# picotouch_synth.net
KiCad netlist of a schematic drawn in EAGLE
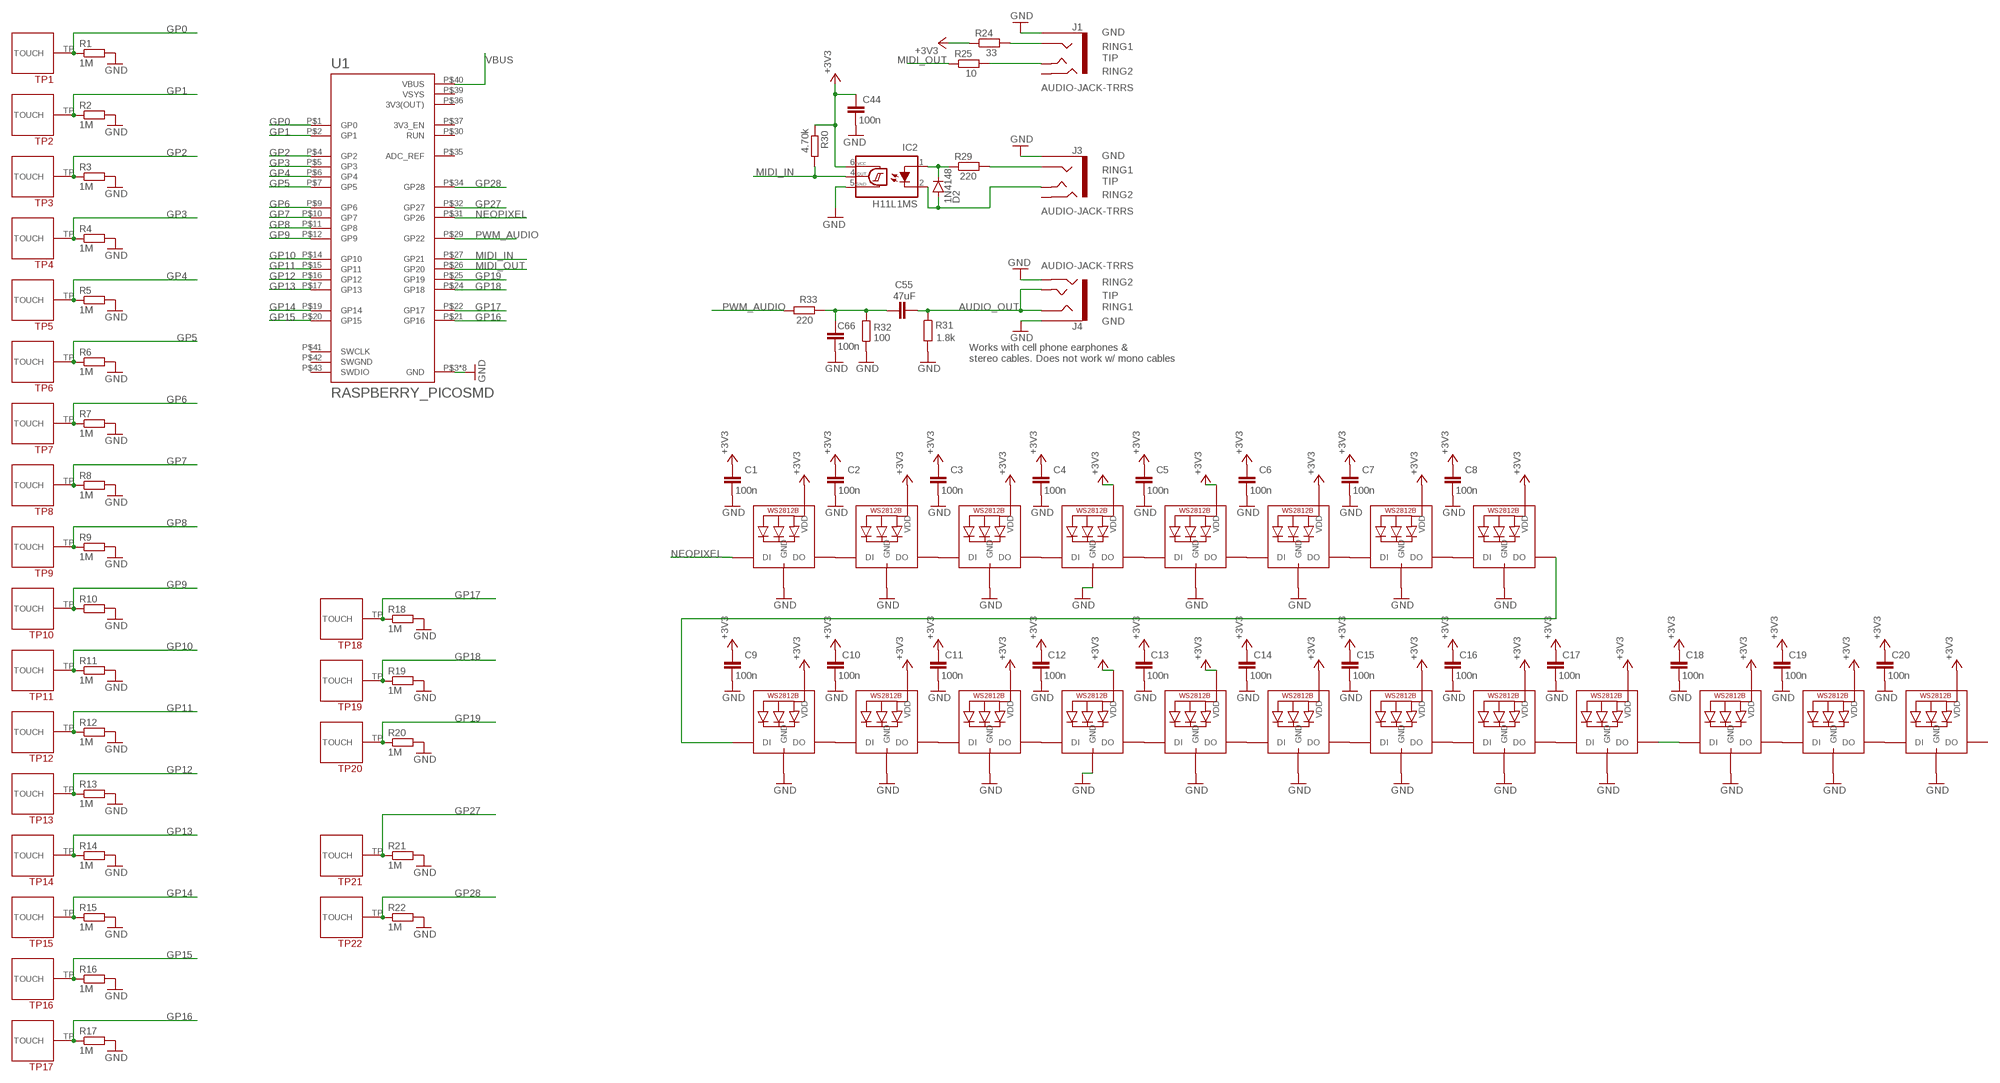
[diagram p0: schematic, sheet 1]

(export (version "E")
  (design (tool "Eeschema 10.0.6"))
  (components
    (comp (ref "C1")
      (value "100n")
      (footprint "eagle-import:C0603")
      (libsource (lib "eagle-import") (part "C-EUC0603"))
    )
    (comp (ref "C2")
      (value "100n")
      (footprint "eagle-import:C0603")
      (libsource (lib "eagle-import") (part "C-EUC0603"))
    )
    (comp (ref "C3")
      (value "100n")
      (footprint "eagle-import:C0603")
      (libsource (lib "eagle-import") (part "C-EUC0603"))
    )
    (comp (ref "C4")
      (value "100n")
      (footprint "eagle-import:C0603")
      (libsource (lib "eagle-import") (part "C-EUC0603"))
    )
    (comp (ref "C5")
      (value "100n")
      (footprint "eagle-import:C0603")
      (libsource (lib "eagle-import") (part "C-EUC0603"))
    )
    (comp (ref "C6")
      (value "100n")
      (footprint "eagle-import:C0603")
      (libsource (lib "eagle-import") (part "C-EUC0603"))
    )
    (comp (ref "C7")
      (value "100n")
      (footprint "eagle-import:C0603")
      (libsource (lib "eagle-import") (part "C-EUC0603"))
    )
    (comp (ref "C8")
      (value "100n")
      (footprint "eagle-import:C0603")
      (libsource (lib "eagle-import") (part "C-EUC0603"))
    )
    (comp (ref "C9")
      (value "100n")
      (footprint "eagle-import:C0603")
      (libsource (lib "eagle-import") (part "C-EUC0603"))
    )
    (comp (ref "C10")
      (value "100n")
      (footprint "eagle-import:C0603")
      (libsource (lib "eagle-import") (part "C-EUC0603"))
    )
    (comp (ref "C11")
      (value "100n")
      (footprint "eagle-import:C0603")
      (libsource (lib "eagle-import") (part "C-EUC0603"))
    )
    (comp (ref "C12")
      (value "100n")
      (footprint "eagle-import:C0603")
      (libsource (lib "eagle-import") (part "C-EUC0603"))
    )
    (comp (ref "C13")
      (value "100n")
      (footprint "eagle-import:C0603")
      (libsource (lib "eagle-import") (part "C-EUC0603"))
    )
    (comp (ref "C14")
      (value "100n")
      (footprint "eagle-import:C0603")
      (libsource (lib "eagle-import") (part "C-EUC0603"))
    )
    (comp (ref "C15")
      (value "100n")
      (footprint "eagle-import:C0603")
      (libsource (lib "eagle-import") (part "C-EUC0603"))
    )
    (comp (ref "C16")
      (value "100n")
      (footprint "eagle-import:C0603")
      (libsource (lib "eagle-import") (part "C-EUC0603"))
    )
    (comp (ref "C17")
      (value "100n")
      (footprint "eagle-import:C0603")
      (libsource (lib "eagle-import") (part "C-EUC0603"))
    )
    (comp (ref "C18")
      (value "100n")
      (footprint "eagle-import:C0603")
      (libsource (lib "eagle-import") (part "C-EUC0603"))
    )
    (comp (ref "C19")
      (value "100n")
      (footprint "eagle-import:C0603")
      (libsource (lib "eagle-import") (part "C-EUC0603"))
    )
    (comp (ref "C20")
      (value "100n")
      (footprint "eagle-import:C0603")
      (libsource (lib "eagle-import") (part "C-EUC0603"))
    )
    (comp (ref "C44")
      (value "100n")
      (footprint "eagle-import:C0603")
      (libsource (lib "eagle-import") (part "C-EUC0603"))
    )
    (comp (ref "C55")
      (value "47uF")
      (footprint "eagle-import:C0603")
      (libsource (lib "eagle-import") (part "C-EUC0603"))
    )
    (comp (ref "C66")
      (value "100n")
      (footprint "eagle-import:C0603")
      (libsource (lib "eagle-import") (part "C-EUC0603"))
    )
    (comp (ref "D2")
      (value "1N4148")
      (footprint "eagle-import:SOD123")
      (libsource (lib "eagle-import") (part "DIODE-SOD123"))
    )
    (comp (ref "IC2")
      (value "H11L1MS")
      (footprint "eagle-import:DIL6-SMD")
      (libsource (lib "eagle-import") (part "H11LMS1"))
    )
    (comp (ref "J1")
      (value "AUDIO-JACK-TRRS")
      (footprint "eagle-import:PJ-320D_SPARKFUN")
      (fields (field (name "MPN") "PJ-320D"))
      (libsource (lib "eagle-import") (part "AUDIO-JACK-TRRS"))
    )
    (comp (ref "J3")
      (value "AUDIO-JACK-TRRS")
      (footprint "eagle-import:PJ-320D_SPARKFUN")
      (fields (field (name "MPN") "PJ-320D"))
      (libsource (lib "eagle-import") (part "AUDIO-JACK-TRRS"))
    )
    (comp (ref "J4")
      (value "AUDIO-JACK-TRRS")
      (footprint "eagle-import:PJ-320D_SPARKFUN")
      (fields (field (name "MPN") "PJ-320D") (field (name "LCSC") "C431535"))
      (libsource (lib "eagle-import") (part "AUDIO-JACK-TRRS"))
    )
    (comp (ref "LED1")
      (value "WS2812B3535")
      (footprint "eagle-import:LED3535")
      (libsource (lib "eagle-import") (part "WS2812B3535"))
    )
    (comp (ref "LED2")
      (value "WS2812B3535")
      (footprint "eagle-import:LED3535")
      (libsource (lib "eagle-import") (part "WS2812B3535"))
    )
    (comp (ref "LED3")
      (value "WS2812B3535")
      (footprint "eagle-import:LED3535")
      (libsource (lib "eagle-import") (part "WS2812B3535"))
    )
    (comp (ref "LED4")
      (value "WS2812B3535")
      (footprint "eagle-import:LED3535")
      (libsource (lib "eagle-import") (part "WS2812B3535"))
    )
    (comp (ref "LED5")
      (value "WS2812B3535")
      (footprint "eagle-import:LED3535")
      (libsource (lib "eagle-import") (part "WS2812B3535"))
    )
    (comp (ref "LED6")
      (value "WS2812B3535")
      (footprint "eagle-import:LED3535")
      (libsource (lib "eagle-import") (part "WS2812B3535"))
    )
    (comp (ref "LED7")
      (value "WS2812B3535")
      (footprint "eagle-import:LED3535")
      (libsource (lib "eagle-import") (part "WS2812B3535"))
    )
    (comp (ref "LED8")
      (value "WS2812B3535")
      (footprint "eagle-import:LED3535")
      (libsource (lib "eagle-import") (part "WS2812B3535"))
    )
    (comp (ref "LED9")
      (value "WS2812B3535")
      (footprint "eagle-import:LED3535")
      (libsource (lib "eagle-import") (part "WS2812B3535"))
    )
    (comp (ref "LED10")
      (value "WS2812B3535")
      (footprint "eagle-import:LED3535")
      (libsource (lib "eagle-import") (part "WS2812B3535"))
    )
    (comp (ref "LED11")
      (value "WS2812B3535")
      (footprint "eagle-import:LED3535")
      (libsource (lib "eagle-import") (part "WS2812B3535"))
    )
    (comp (ref "LED12")
      (value "WS2812B3535")
      (footprint "eagle-import:LED3535")
      (libsource (lib "eagle-import") (part "WS2812B3535"))
    )
    (comp (ref "LED13")
      (value "WS2812B3535")
      (footprint "eagle-import:LED3535")
      (libsource (lib "eagle-import") (part "WS2812B3535"))
    )
    (comp (ref "LED14")
      (value "WS2812B3535")
      (footprint "eagle-import:LED3535")
      (libsource (lib "eagle-import") (part "WS2812B3535"))
    )
    (comp (ref "LED15")
      (value "WS2812B3535")
      (footprint "eagle-import:LED3535")
      (libsource (lib "eagle-import") (part "WS2812B3535"))
    )
    (comp (ref "LED16")
      (value "WS2812B3535")
      (footprint "eagle-import:LED3535")
      (libsource (lib "eagle-import") (part "WS2812B3535"))
    )
    (comp (ref "LED17")
      (value "WS2812B3535")
      (footprint "eagle-import:LED3535")
      (libsource (lib "eagle-import") (part "WS2812B3535"))
    )
    (comp (ref "LED18")
      (value "WS2812B3535")
      (footprint "eagle-import:LED3535")
      (libsource (lib "eagle-import") (part "WS2812B3535"))
    )
    (comp (ref "LED19")
      (value "WS2812B3535")
      (footprint "eagle-import:LED3535")
      (libsource (lib "eagle-import") (part "WS2812B3535"))
    )
    (comp (ref "LED20")
      (value "WS2812B3535")
      (footprint "eagle-import:LED3535")
      (libsource (lib "eagle-import") (part "WS2812B3535"))
    )
    (comp (ref "R1")
      (value "1M")
      (footprint "eagle-import:R0805")
      (libsource (lib "eagle-import") (part "R-EU_R0805"))
    )
    (comp (ref "R2")
      (value "1M")
      (footprint "eagle-import:R0805")
      (libsource (lib "eagle-import") (part "R-EU_R0805"))
    )
    (comp (ref "R3")
      (value "1M")
      (footprint "eagle-import:R0805")
      (libsource (lib "eagle-import") (part "R-EU_R0805"))
    )
    (comp (ref "R4")
      (value "1M")
      (footprint "eagle-import:R0805")
      (libsource (lib "eagle-import") (part "R-EU_R0805"))
    )
    (comp (ref "R5")
      (value "1M")
      (footprint "eagle-import:R0805")
      (libsource (lib "eagle-import") (part "R-EU_R0805"))
    )
    (comp (ref "R6")
      (value "1M")
      (footprint "eagle-import:R0805")
      (libsource (lib "eagle-import") (part "R-EU_R0805"))
    )
    (comp (ref "R7")
      (value "1M")
      (footprint "eagle-import:R0805")
      (libsource (lib "eagle-import") (part "R-EU_R0805"))
    )
    (comp (ref "R8")
      (value "1M")
      (footprint "eagle-import:R0805")
      (libsource (lib "eagle-import") (part "R-EU_R0805"))
    )
    (comp (ref "R9")
      (value "1M")
      (footprint "eagle-import:R0805")
      (libsource (lib "eagle-import") (part "R-EU_R0805"))
    )
    (comp (ref "R10")
      (value "R-EU_R0805")
      (footprint "eagle-import:R0805")
      (libsource (lib "eagle-import") (part "R-EU_R0805"))
    )
    (comp (ref "R11")
      (value "1M")
      (footprint "eagle-import:R0805")
      (libsource (lib "eagle-import") (part "R-EU_R0805"))
    )
    (comp (ref "R12")
      (value "1M")
      (footprint "eagle-import:R0805")
      (libsource (lib "eagle-import") (part "R-EU_R0805"))
    )
    (comp (ref "R13")
      (value "1M")
      (footprint "eagle-import:R0805")
      (libsource (lib "eagle-import") (part "R-EU_R0805"))
    )
    (comp (ref "R14")
      (value "1M")
      (footprint "eagle-import:R0805")
      (libsource (lib "eagle-import") (part "R-EU_R0805"))
    )
    (comp (ref "R15")
      (value "1M")
      (footprint "eagle-import:R0805")
      (libsource (lib "eagle-import") (part "R-EU_R0805"))
    )
    (comp (ref "R16")
      (value "1M")
      (footprint "eagle-import:R0805")
      (libsource (lib "eagle-import") (part "R-EU_R0805"))
    )
    (comp (ref "R17")
      (value "1M")
      (footprint "eagle-import:R0805")
      (libsource (lib "eagle-import") (part "R-EU_R0805"))
    )
    (comp (ref "R18")
      (value "1M")
      (footprint "eagle-import:R0603")
      (libsource (lib "eagle-import") (part "R-EU_R0603"))
    )
    (comp (ref "R19")
      (value "1M")
      (footprint "eagle-import:R0603")
      (libsource (lib "eagle-import") (part "R-EU_R0603"))
    )
    (comp (ref "R20")
      (value "1M")
      (footprint "eagle-import:R0603")
      (libsource (lib "eagle-import") (part "R-EU_R0603"))
    )
    (comp (ref "R21")
      (value "1M")
      (footprint "eagle-import:R0603")
      (libsource (lib "eagle-import") (part "R-EU_R0603"))
    )
    (comp (ref "R22")
      (value "1M")
      (footprint "eagle-import:R0603")
      (libsource (lib "eagle-import") (part "R-EU_R0603"))
    )
    (comp (ref "R24")
      (value "33")
      (footprint "eagle-import:R0603")
      (libsource (lib "eagle-import") (part "R-EU_R0603"))
    )
    (comp (ref "R25")
      (value "10")
      (footprint "eagle-import:R0603")
      (libsource (lib "eagle-import") (part "R-EU_R0603"))
    )
    (comp (ref "R29")
      (value "220")
      (footprint "eagle-import:R0603")
      (libsource (lib "eagle-import") (part "R-EU_R0603"))
    )
    (comp (ref "R30")
      (value "4.70k")
      (footprint "eagle-import:R0603")
      (libsource (lib "eagle-import") (part "R-EU_R0603"))
    )
    (comp (ref "R31")
      (value "1.8k")
      (footprint "eagle-import:R0603")
      (libsource (lib "eagle-import") (part "R-EU_R0603"))
    )
    (comp (ref "R32")
      (value "100")
      (footprint "eagle-import:R0603")
      (libsource (lib "eagle-import") (part "R-EU_R0603"))
    )
    (comp (ref "R33")
      (value "220")
      (footprint "eagle-import:R0603")
      (libsource (lib "eagle-import") (part "R-EU_R0603"))
    )
    (comp (ref "TP1")
      (value "TOUCHPADA")
      (footprint "eagle-import:TOUCHPADA")
      (libsource (lib "eagle-import") (part "TOUCHPADA"))
    )
    (comp (ref "TP2")
      (value "TOUCHPADA")
      (footprint "eagle-import:TOUCHPADA")
      (libsource (lib "eagle-import") (part "TOUCHPADA"))
    )
    (comp (ref "TP3")
      (value "TOUCHPADA")
      (footprint "eagle-import:TOUCHPADA")
      (libsource (lib "eagle-import") (part "TOUCHPADA"))
    )
    (comp (ref "TP4")
      (value "TOUCHPADA")
      (footprint "eagle-import:TOUCHPADA")
      (libsource (lib "eagle-import") (part "TOUCHPADA"))
    )
    (comp (ref "TP5")
      (value "TOUCHPADA")
      (footprint "eagle-import:TOUCHPADA")
      (libsource (lib "eagle-import") (part "TOUCHPADA"))
    )
    (comp (ref "TP6")
      (value "TOUCHPADA")
      (footprint "eagle-import:TOUCHPADA")
      (libsource (lib "eagle-import") (part "TOUCHPADA"))
    )
    (comp (ref "TP7")
      (value "TOUCHPADA")
      (footprint "eagle-import:TOUCHPADA")
      (libsource (lib "eagle-import") (part "TOUCHPADA"))
    )
    (comp (ref "TP8")
      (value "TOUCHPADA")
      (footprint "eagle-import:TOUCHPADA")
      (libsource (lib "eagle-import") (part "TOUCHPADA"))
    )
    (comp (ref "TP9")
      (value "TOUCHPADA")
      (footprint "eagle-import:TOUCHPADA")
      (libsource (lib "eagle-import") (part "TOUCHPADA"))
    )
    (comp (ref "TP10")
      (value "TOUCHPADA")
      (footprint "eagle-import:TOUCHPADA")
      (libsource (lib "eagle-import") (part "TOUCHPADA"))
    )
    (comp (ref "TP11")
      (value "TOUCHPADA")
      (footprint "eagle-import:TOUCHPADA")
      (libsource (lib "eagle-import") (part "TOUCHPADA"))
    )
    (comp (ref "TP12")
      (value "TOUCHPADA")
      (footprint "eagle-import:TOUCHPADA")
      (libsource (lib "eagle-import") (part "TOUCHPADA"))
    )
    (comp (ref "TP13")
      (value "TOUCHPADA")
      (footprint "eagle-import:TOUCHPADA")
      (libsource (lib "eagle-import") (part "TOUCHPADA"))
    )
    (comp (ref "TP14")
      (value "TOUCHPADA")
      (footprint "eagle-import:TOUCHPADA")
      (libsource (lib "eagle-import") (part "TOUCHPADA"))
    )
    (comp (ref "TP15")
      (value "TOUCHPADA")
      (footprint "eagle-import:TOUCHPADA")
      (libsource (lib "eagle-import") (part "TOUCHPADA"))
    )
    (comp (ref "TP16")
      (value "TOUCHPADA")
      (footprint "eagle-import:TOUCHPADA")
      (libsource (lib "eagle-import") (part "TOUCHPADA"))
    )
    (comp (ref "TP17")
      (value "TOUCHPADA")
      (footprint "eagle-import:TOUCHPADA")
      (libsource (lib "eagle-import") (part "TOUCHPADA"))
    )
    (comp (ref "TP18")
      (value "TOUCHPADB")
      (footprint "eagle-import:TOUCHPADB")
      (libsource (lib "eagle-import") (part "TOUCHPADB"))
    )
    (comp (ref "TP19")
      (value "TOUCHPADB")
      (footprint "eagle-import:TOUCHPADB")
      (libsource (lib "eagle-import") (part "TOUCHPADB"))
    )
    (comp (ref "TP20")
      (value "TOUCHPADB")
      (footprint "eagle-import:TOUCHPADB")
      (libsource (lib "eagle-import") (part "TOUCHPADB"))
    )
    (comp (ref "TP21")
      (value "TOUCHPADB")
      (footprint "eagle-import:TOUCHPADB")
      (libsource (lib "eagle-import") (part "TOUCHPADB"))
    )
    (comp (ref "TP22")
      (value "TOUCHPADB")
      (footprint "eagle-import:TOUCHPADB")
      (libsource (lib "eagle-import") (part "TOUCHPADB"))
    )
    (comp (ref "U1")
      (value "RASPBERRY_PICOSMD")
      (footprint "eagle-import:PICO-PKG-SMD")
      (libsource (lib "eagle-import") (part "RASPBERRY_PICOSMD"))
    )
  )
  (nets
    (net (code "1") (name "+3V3") (class "Default")
      (node (ref "C1") (pin "1") (pinfunction "1_1") (pintype "passive"))
      (node (ref "C10") (pin "1") (pinfunction "1_1") (pintype "passive"))
      (node (ref "C11") (pin "1") (pinfunction "1_1") (pintype "passive"))
      (node (ref "C12") (pin "1") (pinfunction "1_1") (pintype "passive"))
      (node (ref "C13") (pin "1") (pinfunction "1_1") (pintype "passive"))
      (node (ref "C14") (pin "1") (pinfunction "1_1") (pintype "passive"))
      (node (ref "C15") (pin "1") (pinfunction "1_1") (pintype "passive"))
      (node (ref "C16") (pin "1") (pinfunction "1_1") (pintype "passive"))
      (node (ref "C17") (pin "1") (pinfunction "1_1") (pintype "passive"))
      (node (ref "C18") (pin "1") (pinfunction "1_1") (pintype "passive"))
      (node (ref "C19") (pin "1") (pinfunction "1_1") (pintype "passive"))
      (node (ref "C2") (pin "1") (pinfunction "1_1") (pintype "passive"))
      (node (ref "C20") (pin "1") (pinfunction "1_1") (pintype "passive"))
      (node (ref "C3") (pin "1") (pinfunction "1_1") (pintype "passive"))
      (node (ref "C4") (pin "1") (pinfunction "1_1") (pintype "passive"))
      (node (ref "C44") (pin "1") (pinfunction "1_1") (pintype "passive"))
      (node (ref "C5") (pin "1") (pinfunction "1_1") (pintype "passive"))
      (node (ref "C6") (pin "1") (pinfunction "1_1") (pintype "passive"))
      (node (ref "C7") (pin "1") (pinfunction "1_1") (pintype "passive"))
      (node (ref "C8") (pin "1") (pinfunction "1_1") (pintype "passive"))
      (node (ref "C9") (pin "1") (pinfunction "1_1") (pintype "passive"))
      (node (ref "IC2") (pin "6") (pinfunction "VCC_6") (pintype "power_in"))
      (node (ref "LED1") (pin "2") (pinfunction "VDD_2") (pintype "power_in"))
      (node (ref "LED10") (pin "2") (pinfunction "VDD_2") (pintype "power_in"))
      (node (ref "LED11") (pin "2") (pinfunction "VDD_2") (pintype "power_in"))
      (node (ref "LED12") (pin "2") (pinfunction "VDD_2") (pintype "power_in"))
      (node (ref "LED13") (pin "2") (pinfunction "VDD_2") (pintype "power_in"))
      (node (ref "LED14") (pin "2") (pinfunction "VDD_2") (pintype "power_in"))
      (node (ref "LED15") (pin "2") (pinfunction "VDD_2") (pintype "power_in"))
      (node (ref "LED16") (pin "2") (pinfunction "VDD_2") (pintype "power_in"))
      (node (ref "LED17") (pin "2") (pinfunction "VDD_2") (pintype "power_in"))
      (node (ref "LED18") (pin "2") (pinfunction "VDD_2") (pintype "power_in"))
      (node (ref "LED19") (pin "2") (pinfunction "VDD_2") (pintype "power_in"))
      (node (ref "LED2") (pin "2") (pinfunction "VDD_2") (pintype "power_in"))
      (node (ref "LED20") (pin "2") (pinfunction "VDD_2") (pintype "power_in"))
      (node (ref "LED3") (pin "2") (pinfunction "VDD_2") (pintype "power_in"))
      (node (ref "LED4") (pin "2") (pinfunction "VDD_2") (pintype "power_in"))
      (node (ref "LED5") (pin "2") (pinfunction "VDD_2") (pintype "power_in"))
      (node (ref "LED6") (pin "2") (pinfunction "VDD_2") (pintype "power_in"))
      (node (ref "LED7") (pin "2") (pinfunction "VDD_2") (pintype "power_in"))
      (node (ref "LED8") (pin "2") (pinfunction "VDD_2") (pintype "power_in"))
      (node (ref "LED9") (pin "2") (pinfunction "VDD_2") (pintype "power_in"))
      (node (ref "R24") (pin "1") (pinfunction "1_1") (pintype "passive"))
      (node (ref "R30") (pin "1") (pinfunction "1_1") (pintype "passive"))
    )
    (net (code "2") (name "/3V3(OUT)") (class "Default")
      (node (ref "U1") (pin "P$36") (pinfunction "3V3(OUT)_P$36") (pintype "power_in"))
    )
    (net (code "3") (name "/AUDIO_OUT") (class "Default")
      (node (ref "C55") (pin "2") (pinfunction "2_2") (pintype "passive"))
      (node (ref "J4") (pin "RING1") (pinfunction "RING1_RING1") (pintype "bidirectional"))
      (node (ref "J4") (pin "TIP") (pinfunction "TIP_TIP") (pintype "bidirectional"))
      (node (ref "R31") (pin "1") (pinfunction "1_1") (pintype "passive"))
    )
    (net (code "4") (name "/GP0") (class "Default")
      (node (ref "R1") (pin "1") (pinfunction "1_1") (pintype "passive"))
      (node (ref "TP1") (pin "TP") (pinfunction "TOUCH_TP") (pintype "bidirectional"))
      (node (ref "U1") (pin "P$1") (pinfunction "GP0_P$1") (pintype "bidirectional"))
    )
    (net (code "5") (name "/GP1") (class "Default")
      (node (ref "R2") (pin "1") (pinfunction "1_1") (pintype "passive"))
      (node (ref "TP2") (pin "TP") (pinfunction "TOUCH_TP") (pintype "bidirectional"))
      (node (ref "U1") (pin "P$2") (pinfunction "GP1_P$2") (pintype "bidirectional"))
    )
    (net (code "6") (name "/GP2") (class "Default")
      (node (ref "R3") (pin "1") (pinfunction "1_1") (pintype "passive"))
      (node (ref "TP3") (pin "TP") (pinfunction "TOUCH_TP") (pintype "bidirectional"))
      (node (ref "U1") (pin "P$4") (pinfunction "GP2_P$4") (pintype "bidirectional"))
    )
    (net (code "7") (name "/GP3") (class "Default")
      (node (ref "R4") (pin "1") (pinfunction "1_1") (pintype "passive"))
      (node (ref "TP4") (pin "TP") (pinfunction "TOUCH_TP") (pintype "bidirectional"))
      (node (ref "U1") (pin "P$5") (pinfunction "GP3_P$5") (pintype "bidirectional"))
    )
    (net (code "8") (name "/GP4") (class "Default")
      (node (ref "R5") (pin "1") (pinfunction "1_1") (pintype "passive"))
      (node (ref "TP5") (pin "TP") (pinfunction "TOUCH_TP") (pintype "bidirectional"))
      (node (ref "U1") (pin "P$6") (pinfunction "GP4_P$6") (pintype "bidirectional"))
    )
    (net (code "9") (name "/GP5") (class "Default")
      (node (ref "R6") (pin "1") (pinfunction "1_1") (pintype "passive"))
      (node (ref "TP6") (pin "TP") (pinfunction "TOUCH_TP") (pintype "bidirectional"))
      (node (ref "U1") (pin "P$7") (pinfunction "GP5_P$7") (pintype "bidirectional"))
    )
    (net (code "10") (name "/GP6") (class "Default")
      (node (ref "R7") (pin "1") (pinfunction "1_1") (pintype "passive"))
      (node (ref "TP7") (pin "TP") (pinfunction "TOUCH_TP") (pintype "bidirectional"))
      (node (ref "U1") (pin "P$9") (pinfunction "GP6_P$9") (pintype "bidirectional"))
    )
    (net (code "11") (name "/GP7") (class "Default")
      (node (ref "R8") (pin "1") (pinfunction "1_1") (pintype "passive"))
      (node (ref "TP8") (pin "TP") (pinfunction "TOUCH_TP") (pintype "bidirectional"))
      (node (ref "U1") (pin "P$10") (pinfunction "GP7_P$10") (pintype "bidirectional"))
    )
    (net (code "12") (name "/GP8") (class "Default")
      (node (ref "R9") (pin "1") (pinfunction "1_1") (pintype "passive"))
      (node (ref "TP9") (pin "TP") (pinfunction "TOUCH_TP") (pintype "bidirectional"))
      (node (ref "U1") (pin "P$11") (pinfunction "GP8_P$11") (pintype "bidirectional"))
    )
    (net (code "13") (name "/GP9") (class "Default")
      (node (ref "R10") (pin "1") (pinfunction "1_1") (pintype "passive"))
      (node (ref "TP10") (pin "TP") (pinfunction "TOUCH_TP") (pintype "bidirectional"))
      (node (ref "U1") (pin "P$12") (pinfunction "GP9_P$12") (pintype "bidirectional"))
    )
    (net (code "14") (name "/GP10") (class "Default")
      (node (ref "R11") (pin "1") (pinfunction "1_1") (pintype "passive"))
      (node (ref "TP11") (pin "TP") (pinfunction "TOUCH_TP") (pintype "bidirectional"))
      (node (ref "U1") (pin "P$14") (pinfunction "GP10_P$14") (pintype "bidirectional"))
    )
    (net (code "15") (name "/GP11") (class "Default")
      (node (ref "R12") (pin "1") (pinfunction "1_1") (pintype "passive"))
      (node (ref "TP12") (pin "TP") (pinfunction "TOUCH_TP") (pintype "bidirectional"))
      (node (ref "U1") (pin "P$15") (pinfunction "GP11_P$15") (pintype "bidirectional"))
    )
    (net (code "16") (name "/GP12") (class "Default")
      (node (ref "R13") (pin "1") (pinfunction "1_1") (pintype "passive"))
      (node (ref "TP13") (pin "TP") (pinfunction "TOUCH_TP") (pintype "bidirectional"))
      (node (ref "U1") (pin "P$16") (pinfunction "GP12_P$16") (pintype "bidirectional"))
    )
    (net (code "17") (name "/GP13") (class "Default")
      (node (ref "R14") (pin "1") (pinfunction "1_1") (pintype "passive"))
      (node (ref "TP14") (pin "TP") (pinfunction "TOUCH_TP") (pintype "bidirectional"))
      (node (ref "U1") (pin "P$17") (pinfunction "GP13_P$17") (pintype "bidirectional"))
    )
    (net (code "18") (name "/GP14") (class "Default")
      (node (ref "R15") (pin "1") (pinfunction "1_1") (pintype "passive"))
      (node (ref "TP15") (pin "TP") (pinfunction "TOUCH_TP") (pintype "bidirectional"))
      (node (ref "U1") (pin "P$19") (pinfunction "GP14_P$19") (pintype "bidirectional"))
    )
    (net (code "19") (name "/GP15") (class "Default")
      (node (ref "R16") (pin "1") (pinfunction "1_1") (pintype "passive"))
      (node (ref "TP16") (pin "TP") (pinfunction "TOUCH_TP") (pintype "bidirectional"))
      (node (ref "U1") (pin "P$20") (pinfunction "GP15_P$20") (pintype "bidirectional"))
    )
    (net (code "20") (name "/GP16") (class "Default")
      (node (ref "R17") (pin "1") (pinfunction "1_1") (pintype "passive"))
      (node (ref "TP17") (pin "TP") (pinfunction "TOUCH_TP") (pintype "bidirectional"))
      (node (ref "U1") (pin "P$21") (pinfunction "GP16_P$21") (pintype "bidirectional"))
    )
    (net (code "21") (name "/GP17") (class "Default")
      (node (ref "R18") (pin "1") (pinfunction "1_1") (pintype "passive"))
      (node (ref "TP18") (pin "TP") (pinfunction "TOUCH_TP") (pintype "bidirectional"))
      (node (ref "U1") (pin "P$22") (pinfunction "GP17_P$22") (pintype "bidirectional"))
    )
    (net (code "22") (name "/GP18") (class "Default")
      (node (ref "R19") (pin "1") (pinfunction "1_1") (pintype "passive"))
      (node (ref "TP19") (pin "TP") (pinfunction "TOUCH_TP") (pintype "bidirectional"))
      (node (ref "U1") (pin "P$24") (pinfunction "GP18_P$24") (pintype "bidirectional"))
    )
    (net (code "23") (name "/GP19") (class "Default")
      (node (ref "R20") (pin "1") (pinfunction "1_1") (pintype "passive"))
      (node (ref "TP20") (pin "TP") (pinfunction "TOUCH_TP") (pintype "bidirectional"))
      (node (ref "U1") (pin "P$25") (pinfunction "GP19_P$25") (pintype "bidirectional"))
    )
    (net (code "24") (name "/GP27") (class "Default")
      (node (ref "R21") (pin "1") (pinfunction "1_1") (pintype "passive"))
      (node (ref "TP21") (pin "TP") (pinfunction "TOUCH_TP") (pintype "bidirectional"))
      (node (ref "U1") (pin "P$32") (pinfunction "GP27_P$32") (pintype "bidirectional"))
    )
    (net (code "25") (name "/GP28") (class "Default")
      (node (ref "R22") (pin "1") (pinfunction "1_1") (pintype "passive"))
      (node (ref "TP22") (pin "TP") (pinfunction "TOUCH_TP") (pintype "bidirectional"))
      (node (ref "U1") (pin "P$34") (pinfunction "GP28_P$34") (pintype "bidirectional"))
    )
    (net (code "26") (name "/MIDI_IN") (class "Default")
      (node (ref "IC2") (pin "4") (pinfunction "OUT_4") (pintype "output"))
      (node (ref "R30") (pin "2") (pinfunction "2_2") (pintype "passive"))
      (node (ref "U1") (pin "P$27") (pinfunction "GP21_P$27") (pintype "bidirectional"))
    )
    (net (code "27") (name "/MIDI_OUT") (class "Default")
      (node (ref "R25") (pin "1") (pinfunction "1_1") (pintype "passive"))
      (node (ref "U1") (pin "P$26") (pinfunction "GP20_P$26") (pintype "bidirectional"))
    )
    (net (code "28") (name "/NEOPIXEL") (class "Default")
      (node (ref "LED1") (pin "1") (pinfunction "DI_1") (pintype "input"))
      (node (ref "U1") (pin "P$31") (pinfunction "GP26_P$31") (pintype "bidirectional"))
    )
    (net (code "29") (name "/PWM_AUDIO") (class "Default")
      (node (ref "R33") (pin "2") (pinfunction "2_2") (pintype "passive"))
      (node (ref "U1") (pin "P$29") (pinfunction "GP22_P$29") (pintype "bidirectional"))
    )
    (net (code "30") (name "/SWGND") (class "Default")
      (node (ref "U1") (pin "P$42") (pinfunction "SWGND_P$42") (pintype "power_in"))
    )
    (net (code "31") (name "/VBUS") (class "Default")
      (node (ref "U1") (pin "P$40") (pinfunction "VBUS_P$40") (pintype "power_in"))
    )
    (net (code "32") (name "/VSYS") (class "Default")
      (node (ref "U1") (pin "P$39") (pinfunction "VSYS_P$39") (pintype "power_in"))
    )
    (net (code "33") (name "GND") (class "Default")
      (node (ref "C1") (pin "2") (pinfunction "2_2") (pintype "passive"))
      (node (ref "C10") (pin "2") (pinfunction "2_2") (pintype "passive"))
      (node (ref "C11") (pin "2") (pinfunction "2_2") (pintype "passive"))
      (node (ref "C12") (pin "2") (pinfunction "2_2") (pintype "passive"))
      (node (ref "C13") (pin "2") (pinfunction "2_2") (pintype "passive"))
      (node (ref "C14") (pin "2") (pinfunction "2_2") (pintype "passive"))
      (node (ref "C15") (pin "2") (pinfunction "2_2") (pintype "passive"))
      (node (ref "C16") (pin "2") (pinfunction "2_2") (pintype "passive"))
      (node (ref "C17") (pin "2") (pinfunction "2_2") (pintype "passive"))
      (node (ref "C18") (pin "2") (pinfunction "2_2") (pintype "passive"))
      (node (ref "C19") (pin "2") (pinfunction "2_2") (pintype "passive"))
      (node (ref "C2") (pin "2") (pinfunction "2_2") (pintype "passive"))
      (node (ref "C20") (pin "2") (pinfunction "2_2") (pintype "passive"))
      (node (ref "C3") (pin "2") (pinfunction "2_2") (pintype "passive"))
      (node (ref "C4") (pin "2") (pinfunction "2_2") (pintype "passive"))
      (node (ref "C44") (pin "2") (pinfunction "2_2") (pintype "passive"))
      (node (ref "C5") (pin "2") (pinfunction "2_2") (pintype "passive"))
      (node (ref "C6") (pin "2") (pinfunction "2_2") (pintype "passive"))
      (node (ref "C66") (pin "2") (pinfunction "2_2") (pintype "passive"))
      (node (ref "C7") (pin "2") (pinfunction "2_2") (pintype "passive"))
      (node (ref "C8") (pin "2") (pinfunction "2_2") (pintype "passive"))
      (node (ref "C9") (pin "2") (pinfunction "2_2") (pintype "passive"))
      (node (ref "IC2") (pin "5") (pinfunction "GND_5") (pintype "power_in"))
      (node (ref "J1") (pin "EARTH") (pinfunction "EARTH_EARTH") (pintype "bidirectional"))
      (node (ref "J3") (pin "EARTH") (pinfunction "EARTH_EARTH") (pintype "bidirectional"))
      (node (ref "J4") (pin "EARTH") (pinfunction "EARTH_EARTH") (pintype "bidirectional"))
      (node (ref "J4") (pin "RING2") (pinfunction "RING2_RING2") (pintype "bidirectional"))
      (node (ref "LED1") (pin "4") (pinfunction "GND_4") (pintype "power_in"))
      (node (ref "LED10") (pin "4") (pinfunction "GND_4") (pintype "power_in"))
      (node (ref "LED11") (pin "4") (pinfunction "GND_4") (pintype "power_in"))
      (node (ref "LED12") (pin "4") (pinfunction "GND_4") (pintype "power_in"))
      (node (ref "LED13") (pin "4") (pinfunction "GND_4") (pintype "power_in"))
      (node (ref "LED14") (pin "4") (pinfunction "GND_4") (pintype "power_in"))
      (node (ref "LED15") (pin "4") (pinfunction "GND_4") (pintype "power_in"))
      (node (ref "LED16") (pin "4") (pinfunction "GND_4") (pintype "power_in"))
      (node (ref "LED17") (pin "4") (pinfunction "GND_4") (pintype "power_in"))
      (node (ref "LED18") (pin "4") (pinfunction "GND_4") (pintype "power_in"))
      (node (ref "LED19") (pin "4") (pinfunction "GND_4") (pintype "power_in"))
      (node (ref "LED2") (pin "4") (pinfunction "GND_4") (pintype "power_in"))
      (node (ref "LED20") (pin "4") (pinfunction "GND_4") (pintype "power_in"))
      (node (ref "LED3") (pin "4") (pinfunction "GND_4") (pintype "power_in"))
      (node (ref "LED4") (pin "4") (pinfunction "GND_4") (pintype "power_in"))
      (node (ref "LED5") (pin "4") (pinfunction "GND_4") (pintype "power_in"))
      (node (ref "LED6") (pin "4") (pinfunction "GND_4") (pintype "power_in"))
      (node (ref "LED7") (pin "4") (pinfunction "GND_4") (pintype "power_in"))
      (node (ref "LED8") (pin "4") (pinfunction "GND_4") (pintype "power_in"))
      (node (ref "LED9") (pin "4") (pinfunction "GND_4") (pintype "power_in"))
      (node (ref "R1") (pin "2") (pinfunction "2_2") (pintype "passive"))
      (node (ref "R10") (pin "2") (pinfunction "2_2") (pintype "passive"))
      (node (ref "R11") (pin "2") (pinfunction "2_2") (pintype "passive"))
      (node (ref "R12") (pin "2") (pinfunction "2_2") (pintype "passive"))
      (node (ref "R13") (pin "2") (pinfunction "2_2") (pintype "passive"))
      (node (ref "R14") (pin "2") (pinfunction "2_2") (pintype "passive"))
      (node (ref "R15") (pin "2") (pinfunction "2_2") (pintype "passive"))
      (node (ref "R16") (pin "2") (pinfunction "2_2") (pintype "passive"))
      (node (ref "R17") (pin "2") (pinfunction "2_2") (pintype "passive"))
      (node (ref "R18") (pin "2") (pinfunction "2_2") (pintype "passive"))
      (node (ref "R19") (pin "2") (pinfunction "2_2") (pintype "passive"))
      (node (ref "R2") (pin "2") (pinfunction "2_2") (pintype "passive"))
      (node (ref "R20") (pin "2") (pinfunction "2_2") (pintype "passive"))
      (node (ref "R21") (pin "2") (pinfunction "2_2") (pintype "passive"))
      (node (ref "R22") (pin "2") (pinfunction "2_2") (pintype "passive"))
      (node (ref "R3") (pin "2") (pinfunction "2_2") (pintype "passive"))
      (node (ref "R31") (pin "2") (pinfunction "2_2") (pintype "passive"))
      (node (ref "R32") (pin "1") (pinfunction "1_1") (pintype "passive"))
      (node (ref "R4") (pin "2") (pinfunction "2_2") (pintype "passive"))
      (node (ref "R5") (pin "2") (pinfunction "2_2") (pintype "passive"))
      (node (ref "R6") (pin "2") (pinfunction "2_2") (pintype "passive"))
      (node (ref "R7") (pin "2") (pinfunction "2_2") (pintype "passive"))
      (node (ref "R8") (pin "2") (pinfunction "2_2") (pintype "passive"))
      (node (ref "R9") (pin "2") (pinfunction "2_2") (pintype "passive"))
      (node (ref "U1") (pin "P$13") (pinfunction "GND_P$13") (pintype "power_in"))
      (node (ref "U1") (pin "P$18") (pinfunction "GND_P$18") (pintype "power_in"))
      (node (ref "U1") (pin "P$23") (pinfunction "GND_P$23") (pintype "power_in"))
      (node (ref "U1") (pin "P$28") (pinfunction "GND_P$28") (pintype "power_in"))
      (node (ref "U1") (pin "P$3") (pinfunction "GND_P$3") (pintype "power_in"))
      (node (ref "U1") (pin "P$33") (pinfunction "GND_P$33") (pintype "power_in"))
      (node (ref "U1") (pin "P$38") (pinfunction "GND_P$38") (pintype "power_in"))
      (node (ref "U1") (pin "P$8") (pinfunction "GND_P$8") (pintype "power_in"))
    )
    (net (code "34") (name "Net-(C55-Pad1)") (class "Default")
      (node (ref "C55") (pin "1") (pinfunction "1_1") (pintype "passive"))
      (node (ref "C66") (pin "1") (pinfunction "1_1") (pintype "passive"))
      (node (ref "R32") (pin "2") (pinfunction "2_2") (pintype "passive"))
      (node (ref "R33") (pin "1") (pinfunction "1_1") (pintype "passive"))
    )
    (net (code "35") (name "Net-(IC2-A)") (class "Default")
      (node (ref "D2") (pin "C") (pinfunction "C_C") (pintype "passive"))
      (node (ref "IC2") (pin "1") (pinfunction "A_1") (pintype "passive"))
      (node (ref "R29") (pin "1") (pinfunction "1_1") (pintype "passive"))
    )
    (net (code "36") (name "Net-(IC2-C)") (class "Default")
      (node (ref "D2") (pin "A") (pinfunction "A_A") (pintype "passive"))
      (node (ref "IC2") (pin "2") (pinfunction "C_2") (pintype "passive"))
      (node (ref "J3") (pin "TIP") (pinfunction "TIP_TIP") (pintype "bidirectional"))
    )
    (net (code "37") (name "Net-(J1-PadRING1)") (class "Default")
      (node (ref "J1") (pin "RING1") (pinfunction "RING1_RING1") (pintype "bidirectional"))
      (node (ref "R24") (pin "2") (pinfunction "2_2") (pintype "passive"))
    )
    (net (code "38") (name "Net-(J1-PadTIP)") (class "Default")
      (node (ref "J1") (pin "TIP") (pinfunction "TIP_TIP") (pintype "bidirectional"))
      (node (ref "R25") (pin "2") (pinfunction "2_2") (pintype "passive"))
    )
    (net (code "39") (name "Net-(J3-PadRING1)") (class "Default")
      (node (ref "J3") (pin "RING1") (pinfunction "RING1_RING1") (pintype "bidirectional"))
      (node (ref "R29") (pin "2") (pinfunction "2_2") (pintype "passive"))
    )
    (net (code "40") (name "Net-(LED1-DO)") (class "Default")
      (node (ref "LED1") (pin "3") (pinfunction "DO_3") (pintype "output"))
      (node (ref "LED2") (pin "1") (pinfunction "DI_1") (pintype "input"))
    )
    (net (code "41") (name "Net-(LED2-DO)") (class "Default")
      (node (ref "LED2") (pin "3") (pinfunction "DO_3") (pintype "output"))
      (node (ref "LED3") (pin "1") (pinfunction "DI_1") (pintype "input"))
    )
    (net (code "42") (name "Net-(LED3-DO)") (class "Default")
      (node (ref "LED3") (pin "3") (pinfunction "DO_3") (pintype "output"))
      (node (ref "LED4") (pin "1") (pinfunction "DI_1") (pintype "input"))
    )
    (net (code "43") (name "Net-(LED4-DO)") (class "Default")
      (node (ref "LED4") (pin "3") (pinfunction "DO_3") (pintype "output"))
      (node (ref "LED5") (pin "1") (pinfunction "DI_1") (pintype "input"))
    )
    (net (code "44") (name "Net-(LED5-DO)") (class "Default")
      (node (ref "LED5") (pin "3") (pinfunction "DO_3") (pintype "output"))
      (node (ref "LED6") (pin "1") (pinfunction "DI_1") (pintype "input"))
    )
    (net (code "45") (name "Net-(LED6-DO)") (class "Default")
      (node (ref "LED6") (pin "3") (pinfunction "DO_3") (pintype "output"))
      (node (ref "LED7") (pin "1") (pinfunction "DI_1") (pintype "input"))
    )
    (net (code "46") (name "Net-(LED7-DO)") (class "Default")
      (node (ref "LED7") (pin "3") (pinfunction "DO_3") (pintype "output"))
      (node (ref "LED8") (pin "1") (pinfunction "DI_1") (pintype "input"))
    )
    (net (code "47") (name "Net-(LED8-DO)") (class "Default")
      (node (ref "LED8") (pin "3") (pinfunction "DO_3") (pintype "output"))
      (node (ref "LED9") (pin "1") (pinfunction "DI_1") (pintype "input"))
    )
    (net (code "48") (name "Net-(LED10-DI)") (class "Default")
      (node (ref "LED10") (pin "1") (pinfunction "DI_1") (pintype "input"))
      (node (ref "LED9") (pin "3") (pinfunction "DO_3") (pintype "output"))
    )
    (net (code "49") (name "Net-(LED10-DO)") (class "Default")
      (node (ref "LED10") (pin "3") (pinfunction "DO_3") (pintype "output"))
      (node (ref "LED11") (pin "1") (pinfunction "DI_1") (pintype "input"))
    )
    (net (code "50") (name "Net-(LED11-DO)") (class "Default")
      (node (ref "LED11") (pin "3") (pinfunction "DO_3") (pintype "output"))
      (node (ref "LED12") (pin "1") (pinfunction "DI_1") (pintype "input"))
    )
    (net (code "51") (name "Net-(LED12-DO)") (class "Default")
      (node (ref "LED12") (pin "3") (pinfunction "DO_3") (pintype "output"))
      (node (ref "LED13") (pin "1") (pinfunction "DI_1") (pintype "input"))
    )
    (net (code "52") (name "Net-(LED13-DO)") (class "Default")
      (node (ref "LED13") (pin "3") (pinfunction "DO_3") (pintype "output"))
      (node (ref "LED14") (pin "1") (pinfunction "DI_1") (pintype "input"))
    )
    (net (code "53") (name "Net-(LED14-DO)") (class "Default")
      (node (ref "LED14") (pin "3") (pinfunction "DO_3") (pintype "output"))
      (node (ref "LED15") (pin "1") (pinfunction "DI_1") (pintype "input"))
    )
    (net (code "54") (name "Net-(LED15-DO)") (class "Default")
      (node (ref "LED15") (pin "3") (pinfunction "DO_3") (pintype "output"))
      (node (ref "LED16") (pin "1") (pinfunction "DI_1") (pintype "input"))
    )
    (net (code "55") (name "Net-(LED16-DO)") (class "Default")
      (node (ref "LED16") (pin "3") (pinfunction "DO_3") (pintype "output"))
      (node (ref "LED17") (pin "1") (pinfunction "DI_1") (pintype "input"))
    )
    (net (code "56") (name "Net-(LED17-DO)") (class "Default")
      (node (ref "LED17") (pin "3") (pinfunction "DO_3") (pintype "output"))
      (node (ref "LED18") (pin "1") (pinfunction "DI_1") (pintype "input"))
    )
    (net (code "57") (name "Net-(LED18-DO)") (class "Default")
      (node (ref "LED18") (pin "3") (pinfunction "DO_3") (pintype "output"))
      (node (ref "LED19") (pin "1") (pinfunction "DI_1") (pintype "input"))
    )
    (net (code "58") (name "Net-(LED19-DO)") (class "Default")
      (node (ref "LED19") (pin "3") (pinfunction "DO_3") (pintype "output"))
      (node (ref "LED20") (pin "1") (pinfunction "DI_1") (pintype "input"))
    )
    (net (code "59") (name "unconnected-(J1-PadRING2)") (class "Default")
      (node (ref "J1") (pin "RING2") (pinfunction "RING2_RING2") (pintype "bidirectional"))
    )
    (net (code "60") (name "unconnected-(J3-PadRING2)") (class "Default")
      (node (ref "J3") (pin "RING2") (pinfunction "RING2_RING2") (pintype "bidirectional"))
    )
    (net (code "61") (name "unconnected-(LED20-DO-Pad3)") (class "Default")
      (node (ref "LED20") (pin "3") (pinfunction "DO_3") (pintype "output"))
    )
    (net (code "62") (name "unconnected-(U1-3V3_EN-PadP$37)") (class "Default")
      (node (ref "U1") (pin "P$37") (pinfunction "3V3_EN_P$37") (pintype "input"))
    )
    (net (code "63") (name "unconnected-(U1-ADC_REF-PadP$35)") (class "Default")
      (node (ref "U1") (pin "P$35") (pinfunction "ADC_REF_P$35") (pintype "input"))
    )
    (net (code "64") (name "unconnected-(U1-RUN-PadP$30)") (class "Default")
      (node (ref "U1") (pin "P$30") (pinfunction "RUN_P$30") (pintype "input"))
    )
    (net (code "65") (name "unconnected-(U1-SWCLK-PadP$41)") (class "Default")
      (node (ref "U1") (pin "P$41") (pinfunction "SWCLK_P$41") (pintype "input"))
    )
    (net (code "66") (name "unconnected-(U1-SWDIO-PadP$43)") (class "Default")
      (node (ref "U1") (pin "P$43") (pinfunction "SWDIO_P$43") (pintype "bidirectional"))
    )
  )
)
